# gpio8s5.net
KiCad netlist of a schematic drawn in EAGLE
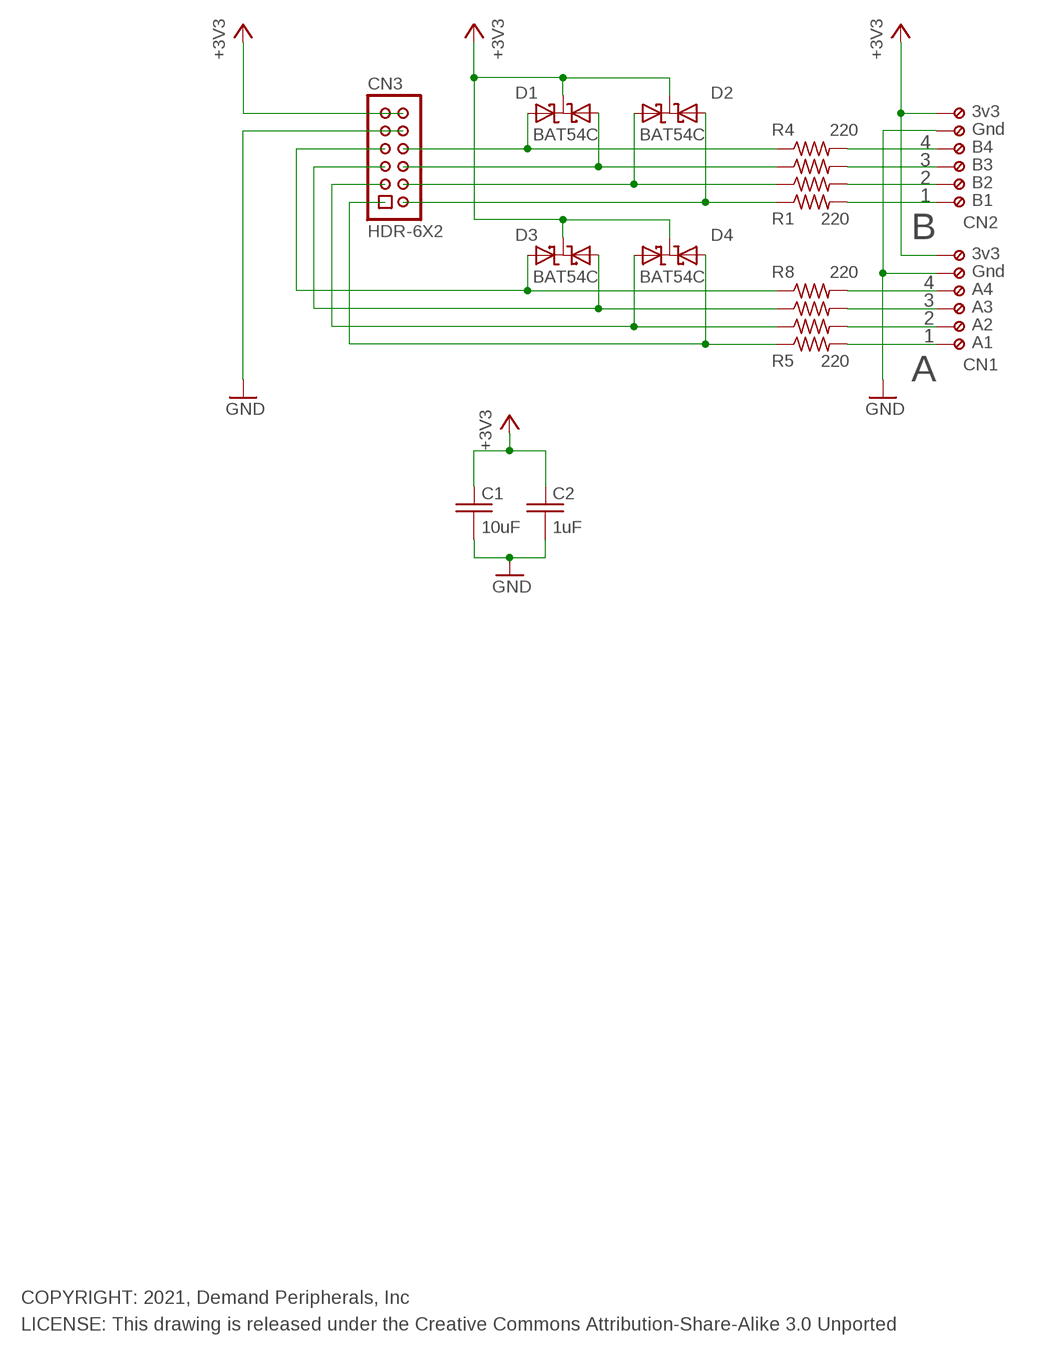
[diagram p0: schematic, sheet 1]

(export (version "E")
  (design (tool "Eeschema 10.0.6"))
  (components
    (comp (ref "C1")
      (value "10uF")
      (footprint "eagle-import:C1206")
      (libsource (lib "eagle-import") (part "C10UF25V_C1206"))
    )
    (comp (ref "C2")
      (value "1uF")
      (footprint "eagle-import:C0603")
      (libsource (lib "eagle-import") (part "C1.0UF_C0603"))
    )
    (comp (ref "CN1")
      (value "TBLK-3.5X6")
      (footprint "eagle-import:TBLK-3.5X6")
      (libsource (lib "eagle-import") (part "TBLK-3.5X6"))
    )
    (comp (ref "CN2")
      (value "TBLK-3.5X6")
      (footprint "eagle-import:TBLK-3.5X6")
      (libsource (lib "eagle-import") (part "TBLK-3.5X6"))
    )
    (comp (ref "CN3")
      (value "HDR-6X2")
      (footprint "eagle-import:HDR-6X2")
      (libsource (lib "eagle-import") (part "HDR-6X2"))
    )
    (comp (ref "D1")
      (value "BAT54C")
      (footprint "eagle-import:SOT23")
      (libsource (lib "eagle-import") (part "BAT54C"))
    )
    (comp (ref "D2")
      (value "BAT54C")
      (footprint "eagle-import:SOT23")
      (libsource (lib "eagle-import") (part "BAT54C"))
    )
    (comp (ref "D3")
      (value "BAT54C")
      (footprint "eagle-import:SOT23")
      (libsource (lib "eagle-import") (part "BAT54C"))
    )
    (comp (ref "D4")
      (value "BAT54C")
      (footprint "eagle-import:SOT23")
      (libsource (lib "eagle-import") (part "BAT54C"))
    )
    (comp (ref "R1")
      (value "220")
      (footprint "eagle-import:R0603")
      (libsource (lib "eagle-import") (part "R220_R0603"))
    )
    (comp (ref "R2")
      (value "220")
      (footprint "eagle-import:R0603")
      (libsource (lib "eagle-import") (part "R220_R0603"))
    )
    (comp (ref "R3")
      (value "220")
      (footprint "eagle-import:R0603")
      (libsource (lib "eagle-import") (part "R220_R0603"))
    )
    (comp (ref "R4")
      (value "220")
      (footprint "eagle-import:R0603")
      (libsource (lib "eagle-import") (part "R220_R0603"))
    )
    (comp (ref "R5")
      (value "220")
      (footprint "eagle-import:R0603")
      (libsource (lib "eagle-import") (part "R220_R0603"))
    )
    (comp (ref "R6")
      (value "220")
      (footprint "eagle-import:R0603")
      (libsource (lib "eagle-import") (part "R220_R0603"))
    )
    (comp (ref "R7")
      (value "220")
      (footprint "eagle-import:R0603")
      (libsource (lib "eagle-import") (part "R220_R0603"))
    )
    (comp (ref "R8")
      (value "220")
      (footprint "eagle-import:R0603")
      (libsource (lib "eagle-import") (part "R220_R0603"))
    )
  )
  (nets
    (net (code "1") (name "+3V3") (class "Default")
      (node (ref "C1") (pin "1") (pinfunction "1_1") (pintype "passive"))
      (node (ref "C2") (pin "1") (pinfunction "1_1") (pintype "passive"))
      (node (ref "CN1") (pin "1") (pinfunction "KL_1") (pintype "passive"))
      (node (ref "CN2") (pin "1") (pinfunction "KL_1") (pintype "passive"))
      (node (ref "CN3") (pin "11") (pinfunction "11_11") (pintype "passive"))
      (node (ref "CN3") (pin "12") (pinfunction "12_12") (pintype "passive"))
      (node (ref "D1") (pin "3") (pinfunction "CC_3") (pintype "passive"))
      (node (ref "D2") (pin "3") (pinfunction "CC_3") (pintype "passive"))
      (node (ref "D3") (pin "3") (pinfunction "CC_3") (pintype "passive"))
      (node (ref "D4") (pin "3") (pinfunction "CC_3") (pintype "passive"))
    )
    (net (code "2") (name "GND") (class "Default")
      (node (ref "C1") (pin "2") (pinfunction "2_2") (pintype "passive"))
      (node (ref "C2") (pin "2") (pinfunction "2_2") (pintype "passive"))
      (node (ref "CN1") (pin "2") (pinfunction "KL1_2") (pintype "passive"))
      (node (ref "CN2") (pin "2") (pinfunction "KL1_2") (pintype "passive"))
      (node (ref "CN3") (pin "10") (pinfunction "10_10") (pintype "passive"))
      (node (ref "CN3") (pin "9") (pinfunction "9_9") (pintype "passive"))
    )
    (net (code "3") (name "Net-(CN1-KL2)") (class "Default")
      (node (ref "CN1") (pin "3") (pinfunction "KL2_3") (pintype "passive"))
      (node (ref "R8") (pin "2") (pinfunction "2_2") (pintype "passive"))
    )
    (net (code "4") (name "Net-(CN1-KL3)") (class "Default")
      (node (ref "CN1") (pin "4") (pinfunction "KL3_4") (pintype "passive"))
      (node (ref "R7") (pin "2") (pinfunction "2_2") (pintype "passive"))
    )
    (net (code "5") (name "Net-(CN1-KL4)") (class "Default")
      (node (ref "CN1") (pin "5") (pinfunction "KL4_5") (pintype "passive"))
      (node (ref "R6") (pin "2") (pinfunction "2_2") (pintype "passive"))
    )
    (net (code "6") (name "Net-(CN1-KL5)") (class "Default")
      (node (ref "CN1") (pin "6") (pinfunction "KL5_6") (pintype "passive"))
      (node (ref "R5") (pin "2") (pinfunction "2_2") (pintype "passive"))
    )
    (net (code "7") (name "Net-(CN2-KL2)") (class "Default")
      (node (ref "CN2") (pin "3") (pinfunction "KL2_3") (pintype "passive"))
      (node (ref "R4") (pin "2") (pinfunction "2_2") (pintype "passive"))
    )
    (net (code "8") (name "Net-(CN2-KL3)") (class "Default")
      (node (ref "CN2") (pin "4") (pinfunction "KL3_4") (pintype "passive"))
      (node (ref "R3") (pin "2") (pinfunction "2_2") (pintype "passive"))
    )
    (net (code "9") (name "Net-(CN2-KL4)") (class "Default")
      (node (ref "CN2") (pin "5") (pinfunction "KL4_5") (pintype "passive"))
      (node (ref "R2") (pin "2") (pinfunction "2_2") (pintype "passive"))
    )
    (net (code "10") (name "Net-(CN2-KL5)") (class "Default")
      (node (ref "CN2") (pin "6") (pinfunction "KL5_6") (pintype "passive"))
      (node (ref "R1") (pin "2") (pinfunction "2_2") (pintype "passive"))
    )
    (net (code "11") (name "Net-(D1-A)") (class "Default")
      (node (ref "CN3") (pin "6") (pinfunction "6_6") (pintype "passive"))
      (node (ref "D1") (pin "2") (pinfunction "A_2") (pintype "passive"))
      (node (ref "R3") (pin "1") (pinfunction "1_1") (pintype "passive"))
    )
    (net (code "12") (name "Net-(D1-A1)") (class "Default")
      (node (ref "CN3") (pin "8") (pinfunction "8_8") (pintype "passive"))
      (node (ref "D1") (pin "1") (pinfunction "A1_1") (pintype "passive"))
      (node (ref "R4") (pin "1") (pinfunction "1_1") (pintype "passive"))
    )
    (net (code "13") (name "Net-(D2-A)") (class "Default")
      (node (ref "CN3") (pin "2") (pinfunction "2_2") (pintype "passive"))
      (node (ref "D2") (pin "2") (pinfunction "A_2") (pintype "passive"))
      (node (ref "R1") (pin "1") (pinfunction "1_1") (pintype "passive"))
    )
    (net (code "14") (name "Net-(D2-A1)") (class "Default")
      (node (ref "CN3") (pin "4") (pinfunction "4_4") (pintype "passive"))
      (node (ref "D2") (pin "1") (pinfunction "A1_1") (pintype "passive"))
      (node (ref "R2") (pin "1") (pinfunction "1_1") (pintype "passive"))
    )
    (net (code "15") (name "Net-(D3-A)") (class "Default")
      (node (ref "CN3") (pin "5") (pinfunction "5_5") (pintype "passive"))
      (node (ref "D3") (pin "2") (pinfunction "A_2") (pintype "passive"))
      (node (ref "R7") (pin "1") (pinfunction "1_1") (pintype "passive"))
    )
    (net (code "16") (name "Net-(D3-A1)") (class "Default")
      (node (ref "CN3") (pin "7") (pinfunction "7_7") (pintype "passive"))
      (node (ref "D3") (pin "1") (pinfunction "A1_1") (pintype "passive"))
      (node (ref "R8") (pin "1") (pinfunction "1_1") (pintype "passive"))
    )
    (net (code "17") (name "Net-(D4-A)") (class "Default")
      (node (ref "CN3") (pin "1") (pinfunction "1_1") (pintype "passive"))
      (node (ref "D4") (pin "2") (pinfunction "A_2") (pintype "passive"))
      (node (ref "R5") (pin "1") (pinfunction "1_1") (pintype "passive"))
    )
    (net (code "18") (name "Net-(D4-A1)") (class "Default")
      (node (ref "CN3") (pin "3") (pinfunction "3_3") (pintype "passive"))
      (node (ref "D4") (pin "1") (pinfunction "A1_1") (pintype "passive"))
      (node (ref "R6") (pin "1") (pinfunction "1_1") (pintype "passive"))
    )
  )
)
